# TARGET_xDOT.net
KiCad netlist of a schematic drawn in EAGLE
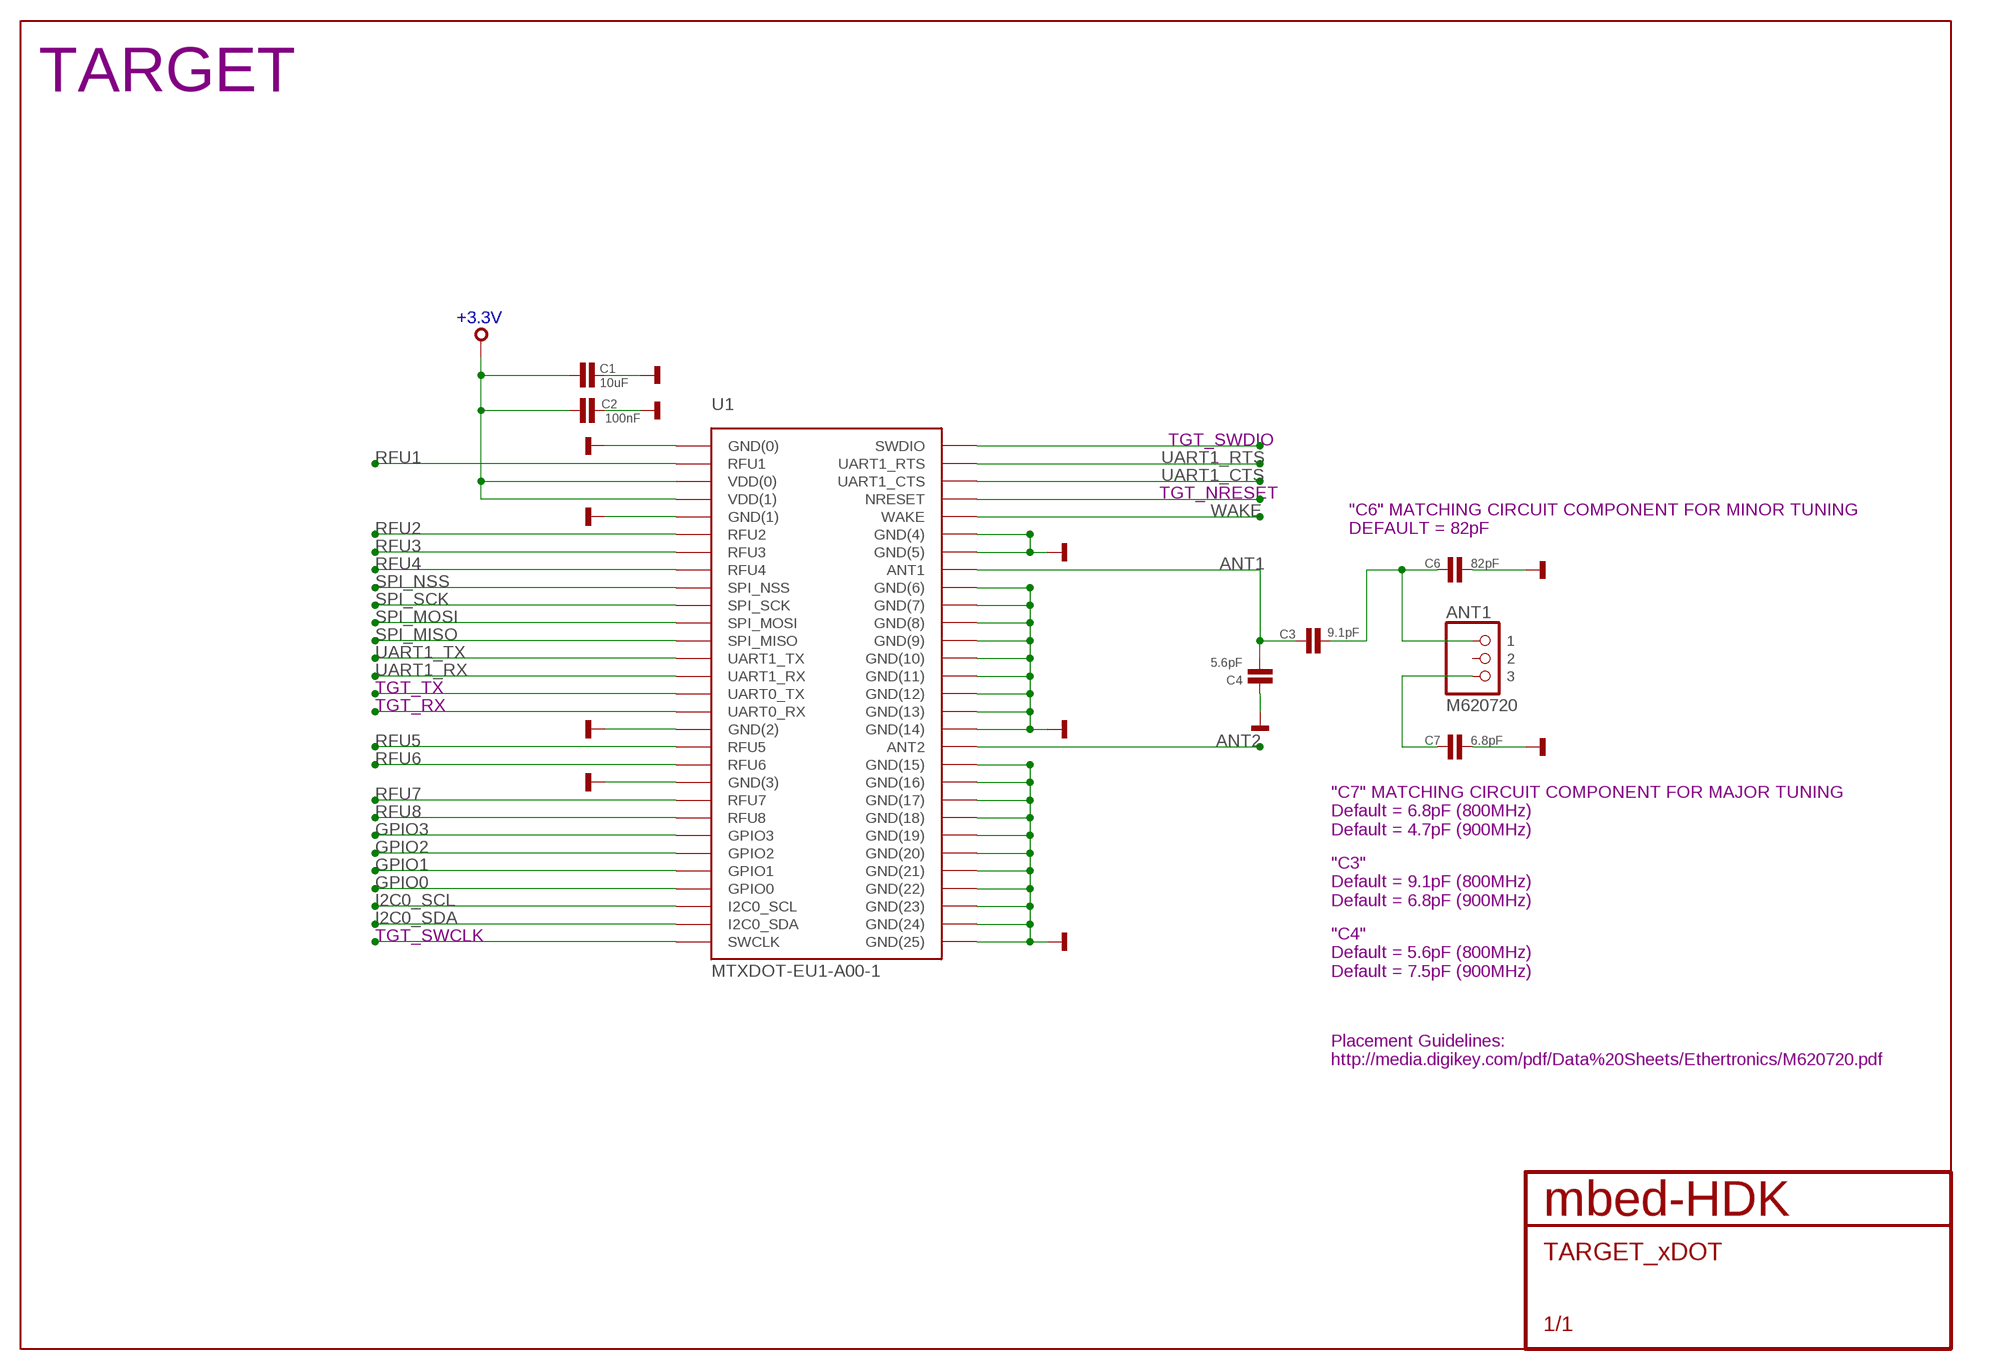
[diagram p0: schematic, sheet 1]

(export (version "E")
  (design (tool "Eeschema 10.0.6"))
  (components
    (comp (ref "ANT1")
      (value "M620720")
      (footprint "eagle-import:M620720")
      (fields (field (name "MF") "Ethertronics"))
      (libsource (lib "eagle-import") (part "M620720"))
    )
    (comp (ref "C1")
      (value "10uF")
      (footprint "eagle-import:0603")
      (libsource (lib "eagle-import") (part "CAPACITOR0603"))
    )
    (comp (ref "C2")
      (value "100nF")
      (footprint "eagle-import:0603")
      (libsource (lib "eagle-import") (part "CAPACITOR0603"))
    )
    (comp (ref "C3")
      (value "9.1pF")
      (footprint "eagle-import:0402")
      (libsource (lib "eagle-import") (part "CAPACITOR0402"))
    )
    (comp (ref "C4")
      (value "5.6pF")
      (footprint "eagle-import:0402")
      (libsource (lib "eagle-import") (part "CAPACITOR0402"))
    )
    (comp (ref "C6")
      (value "82pF")
      (footprint "eagle-import:0402")
      (libsource (lib "eagle-import") (part "CAPACITOR0402"))
    )
    (comp (ref "C7")
      (value "6.8pF")
      (footprint "eagle-import:0402")
      (libsource (lib "eagle-import") (part "CAPACITOR0402"))
    )
    (comp (ref "U1")
      (value "MTXDOT-EU1-A00-1")
      (footprint "eagle-import:MTXDOT-EU1_NA1-A00-1")
      (fields (field (name "MF") "Multi-Tech Systems Inc."))
      (libsource (lib "eagle-import") (part "MTXDOT-EU1-A00-1"))
    )
  )
  (nets
    (net (code "1") (name "+3.3V") (class "Default")
      (node (ref "C1") (pin "1") (pinfunction "P$1_1") (pintype "passive"))
      (node (ref "C2") (pin "1") (pinfunction "P$1_1") (pintype "passive"))
      (node (ref "U1") (pin "P$3") (pinfunction "VDD(0)_P$3") (pintype "bidirectional"))
      (node (ref "U1") (pin "P$4") (pinfunction "VDD(1)_P$4") (pintype "bidirectional"))
    )
    (net (code "2") (name "/ANT1") (class "Default")
      (node (ref "C3") (pin "1") (pinfunction "P$1_1") (pintype "passive"))
      (node (ref "C4") (pin "2") (pinfunction "P$2_2") (pintype "passive"))
      (node (ref "U1") (pin "P$37") (pinfunction "ANT1_P$37") (pintype "bidirectional"))
    )
    (net (code "3") (name "/ANT2") (class "Default")
      (node (ref "U1") (pin "P$47") (pinfunction "ANT2_P$47") (pintype "bidirectional"))
    )
    (net (code "4") (name "/GPIO0") (class "Default")
      (node (ref "U1") (pin "P$26") (pinfunction "GPIO0_P$26") (pintype "bidirectional"))
    )
    (net (code "5") (name "/GPIO1") (class "Default")
      (node (ref "U1") (pin "P$25") (pinfunction "GPIO1_P$25") (pintype "bidirectional"))
    )
    (net (code "6") (name "/GPIO2") (class "Default")
      (node (ref "U1") (pin "P$24") (pinfunction "GPIO2_P$24") (pintype "bidirectional"))
    )
    (net (code "7") (name "/GPIO3") (class "Default")
      (node (ref "U1") (pin "P$23") (pinfunction "GPIO3_P$23") (pintype "bidirectional"))
    )
    (net (code "8") (name "/I2C0_SCL") (class "Default")
      (node (ref "U1") (pin "P$27") (pinfunction "I2C0_SCL_P$27") (pintype "bidirectional"))
    )
    (net (code "9") (name "/I2C0_SDA") (class "Default")
      (node (ref "U1") (pin "P$28") (pinfunction "I2C0_SDA_P$28") (pintype "bidirectional"))
    )
    (net (code "10") (name "/RFU1") (class "Default")
      (node (ref "U1") (pin "P$2") (pinfunction "RFU1_P$2") (pintype "bidirectional"))
    )
    (net (code "11") (name "/RFU2") (class "Default")
      (node (ref "U1") (pin "P$6") (pinfunction "RFU2_P$6") (pintype "bidirectional"))
    )
    (net (code "12") (name "/RFU3") (class "Default")
      (node (ref "U1") (pin "P$7") (pinfunction "RFU3_P$7") (pintype "bidirectional"))
    )
    (net (code "13") (name "/RFU4") (class "Default")
      (node (ref "U1") (pin "P$8") (pinfunction "RFU4_P$8") (pintype "bidirectional"))
    )
    (net (code "14") (name "/RFU5") (class "Default")
      (node (ref "U1") (pin "P$18") (pinfunction "RFU5_P$18") (pintype "bidirectional"))
    )
    (net (code "15") (name "/RFU6") (class "Default")
      (node (ref "U1") (pin "P$19") (pinfunction "RFU6_P$19") (pintype "bidirectional"))
    )
    (net (code "16") (name "/RFU7") (class "Default")
      (node (ref "U1") (pin "P$21") (pinfunction "RFU7_P$21") (pintype "bidirectional"))
    )
    (net (code "17") (name "/RFU8") (class "Default")
      (node (ref "U1") (pin "P$22") (pinfunction "RFU8_P$22") (pintype "bidirectional"))
    )
    (net (code "18") (name "/SPI_MISO") (class "Default")
      (node (ref "U1") (pin "P$12") (pinfunction "SPI_MISO_P$12") (pintype "bidirectional"))
    )
    (net (code "19") (name "/SPI_MOSI") (class "Default")
      (node (ref "U1") (pin "P$11") (pinfunction "SPI_MOSI_P$11") (pintype "bidirectional"))
    )
    (net (code "20") (name "/SPI_NSS") (class "Default")
      (node (ref "U1") (pin "P$9") (pinfunction "SPI_NSS_P$9") (pintype "bidirectional"))
    )
    (net (code "21") (name "/SPI_SCK") (class "Default")
      (node (ref "U1") (pin "P$10") (pinfunction "SPI_SCK_P$10") (pintype "bidirectional"))
    )
    (net (code "22") (name "/TGT_NRESET") (class "Default")
      (node (ref "U1") (pin "P$33") (pinfunction "NRESET_P$33") (pintype "bidirectional"))
    )
    (net (code "23") (name "/TGT_RX") (class "Default")
      (node (ref "U1") (pin "P$16") (pinfunction "UART0_RX_P$16") (pintype "bidirectional"))
    )
    (net (code "24") (name "/TGT_SWCLK") (class "Default")
      (node (ref "U1") (pin "P$29") (pinfunction "SWCLK_P$29") (pintype "bidirectional"))
    )
    (net (code "25") (name "/TGT_SWDIO") (class "Default")
      (node (ref "U1") (pin "P$30") (pinfunction "SWDIO_P$30") (pintype "bidirectional"))
    )
    (net (code "26") (name "/TGT_TX") (class "Default")
      (node (ref "U1") (pin "P$15") (pinfunction "UART0_TX_P$15") (pintype "bidirectional"))
    )
    (net (code "27") (name "/UART1_CTS") (class "Default")
      (node (ref "U1") (pin "P$32") (pinfunction "UART1_CTS_P$32") (pintype "bidirectional"))
    )
    (net (code "28") (name "/UART1_RTS") (class "Default")
      (node (ref "U1") (pin "P$31") (pinfunction "UART1_RTS_P$31") (pintype "bidirectional"))
    )
    (net (code "29") (name "/UART1_RX") (class "Default")
      (node (ref "U1") (pin "P$14") (pinfunction "UART1_RX_P$14") (pintype "bidirectional"))
    )
    (net (code "30") (name "/UART1_TX") (class "Default")
      (node (ref "U1") (pin "P$13") (pinfunction "UART1_TX_P$13") (pintype "bidirectional"))
    )
    (net (code "31") (name "/WAKE") (class "Default")
      (node (ref "U1") (pin "P$34") (pinfunction "WAKE_P$34") (pintype "bidirectional"))
    )
    (net (code "32") (name "GND") (class "Default")
      (node (ref "C1") (pin "2") (pinfunction "P$2_2") (pintype "passive"))
      (node (ref "C2") (pin "2") (pinfunction "P$2_2") (pintype "passive"))
      (node (ref "C4") (pin "1") (pinfunction "P$1_1") (pintype "passive"))
      (node (ref "C6") (pin "1") (pinfunction "P$1_1") (pintype "passive"))
      (node (ref "C7") (pin "1") (pinfunction "P$1_1") (pintype "passive"))
      (node (ref "U1") (pin "P$1") (pinfunction "GND(0)_P$1") (pintype "bidirectional"))
      (node (ref "U1") (pin "P$17") (pinfunction "GND(2)_P$17") (pintype "bidirectional"))
      (node (ref "U1") (pin "P$20") (pinfunction "GND(3)_P$20") (pintype "bidirectional"))
      (node (ref "U1") (pin "P$35") (pinfunction "GND(4)_P$35") (pintype "bidirectional"))
      (node (ref "U1") (pin "P$36") (pinfunction "GND(5)_P$36") (pintype "bidirectional"))
      (node (ref "U1") (pin "P$38") (pinfunction "GND(6)_P$38") (pintype "bidirectional"))
      (node (ref "U1") (pin "P$39") (pinfunction "GND(7)_P$39") (pintype "bidirectional"))
      (node (ref "U1") (pin "P$40") (pinfunction "GND(8)_P$40") (pintype "bidirectional"))
      (node (ref "U1") (pin "P$41") (pinfunction "GND(9)_P$41") (pintype "bidirectional"))
      (node (ref "U1") (pin "P$42") (pinfunction "GND(10)_P$42") (pintype "bidirectional"))
      (node (ref "U1") (pin "P$43") (pinfunction "GND(11)_P$43") (pintype "bidirectional"))
      (node (ref "U1") (pin "P$44") (pinfunction "GND(12)_P$44") (pintype "bidirectional"))
      (node (ref "U1") (pin "P$45") (pinfunction "GND(13)_P$45") (pintype "bidirectional"))
      (node (ref "U1") (pin "P$46") (pinfunction "GND(14)_P$46") (pintype "bidirectional"))
      (node (ref "U1") (pin "P$48") (pinfunction "GND(15)_P$48") (pintype "bidirectional"))
      (node (ref "U1") (pin "P$49") (pinfunction "GND(16)_P$49") (pintype "bidirectional"))
      (node (ref "U1") (pin "P$5") (pinfunction "GND(1)_P$5") (pintype "bidirectional"))
      (node (ref "U1") (pin "P$50") (pinfunction "GND(17)_P$50") (pintype "bidirectional"))
      (node (ref "U1") (pin "P$51") (pinfunction "GND(18)_P$51") (pintype "bidirectional"))
      (node (ref "U1") (pin "P$52") (pinfunction "GND(19)_P$52") (pintype "bidirectional"))
      (node (ref "U1") (pin "P$53") (pinfunction "GND(20)_P$53") (pintype "bidirectional"))
      (node (ref "U1") (pin "P$54") (pinfunction "GND(21)_P$54") (pintype "bidirectional"))
      (node (ref "U1") (pin "P$55") (pinfunction "GND(22)_P$55") (pintype "bidirectional"))
      (node (ref "U1") (pin "P$56") (pinfunction "GND(23)_P$56") (pintype "bidirectional"))
      (node (ref "U1") (pin "P$57") (pinfunction "GND(24)_P$57") (pintype "bidirectional"))
      (node (ref "U1") (pin "P$58") (pinfunction "GND(25)_P$58") (pintype "bidirectional"))
    )
    (net (code "33") (name "Net-(ANT1-1)") (class "Default")
      (node (ref "ANT1") (pin "P$1") (pinfunction "1_P$1") (pintype "passive"))
      (node (ref "C3") (pin "2") (pinfunction "P$2_2") (pintype "passive"))
      (node (ref "C6") (pin "2") (pinfunction "P$2_2") (pintype "passive"))
    )
    (net (code "34") (name "Net-(ANT1-3)") (class "Default")
      (node (ref "ANT1") (pin "P$3") (pinfunction "3_P$3") (pintype "passive"))
      (node (ref "C7") (pin "2") (pinfunction "P$2_2") (pintype "passive"))
    )
    (net (code "35") (name "unconnected-(ANT1-2-PadP$2)") (class "Default")
      (node (ref "ANT1") (pin "P$2") (pinfunction "2_P$2") (pintype "passive"))
    )
  )
)
